# FPGA.net
KiCad netlist of a schematic drawn in Altium Designer
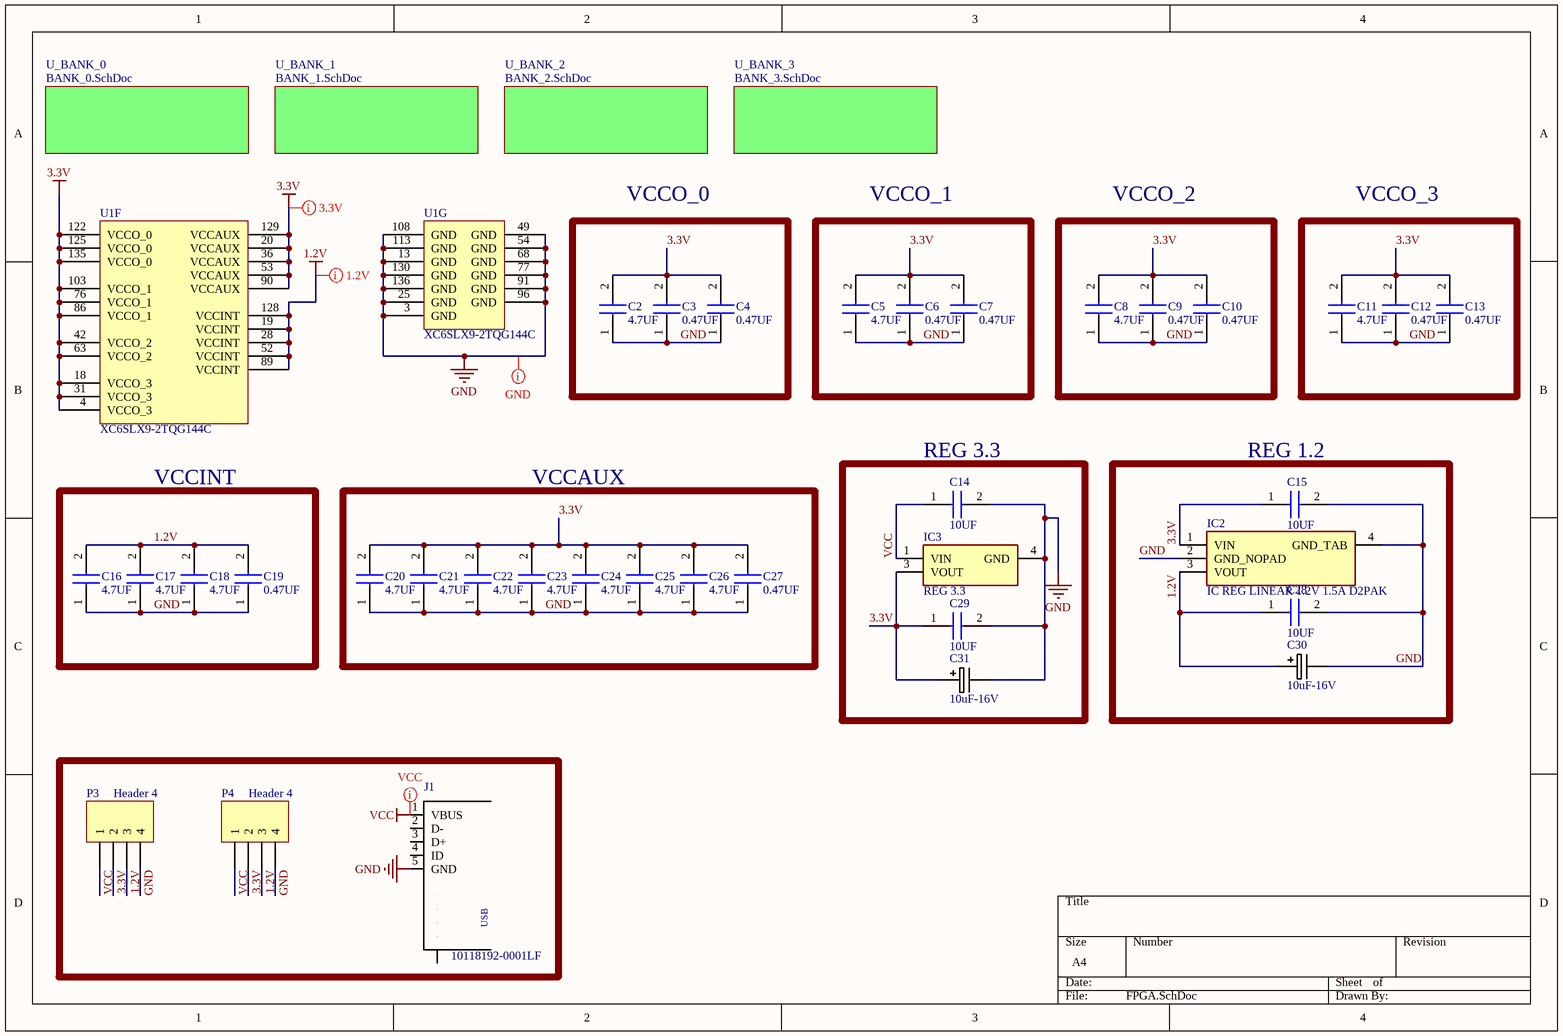
[diagram p0: FPGA.SchDoc]

(export (version "E")
  (design (tool "Eeschema 10.0.6"))
  (components
    (comp (ref "C2")
      (value "4.7UF")
      (footprint "PcbLib1:CAPC2012X135N")
      (description "Capacitor")
      (fields
        (field (name "MANUFACTURER_PART_NUMBER") "885012107013")
        (field (name "MOUSER PART NUMBER") "710-885012107013")
      )
      (libsource (lib "Schlib1_FPGA") (part "CAP CER 4.7UF 16V X5R 0805"))
    )
    (comp (ref "C3")
      (value "0.47UF")
      (footprint "PcbLib1:CAPC2012X135N")
      (description "Capacitor")
      (fields
        (field (name "MANUFACTURER_PART_NUMBER") "885012207049")
        (field (name "MOUSER PART NUMBER") "710-885012207049")
      )
      (libsource (lib "Schlib1_FPGA") (part "CAP CER 0.47UF 16V X7R 0805"))
    )
    (comp (ref "C4")
      (value "0.47UF")
      (footprint "PcbLib1:CAPC2012X135N")
      (description "Capacitor")
      (fields
        (field (name "MANUFACTURER_PART_NUMBER") "885012207049")
        (field (name "MOUSER PART NUMBER") "710-885012207049")
      )
      (libsource (lib "Schlib1_FPGA") (part "CAP CER 0.47UF 16V X7R 0805"))
    )
    (comp (ref "C5")
      (value "4.7UF")
      (footprint "PcbLib1:CAPC2012X135N")
      (description "Capacitor")
      (fields
        (field (name "MANUFACTURER_PART_NUMBER") "885012107013")
        (field (name "MOUSER PART NUMBER") "710-885012107013")
      )
      (libsource (lib "Schlib1_FPGA") (part "CAP CER 4.7UF 16V X5R 0805"))
    )
    (comp (ref "C6")
      (value "0.47UF")
      (footprint "PcbLib1:CAPC2012X135N")
      (description "Capacitor")
      (fields
        (field (name "MANUFACTURER_PART_NUMBER") "885012207049")
        (field (name "MOUSER PART NUMBER") "710-885012207049")
      )
      (libsource (lib "Schlib1_FPGA") (part "CAP CER 0.47UF 16V X7R 0805"))
    )
    (comp (ref "C7")
      (value "0.47UF")
      (footprint "PcbLib1:CAPC2012X135N")
      (description "Capacitor")
      (fields
        (field (name "MANUFACTURER_PART_NUMBER") "885012207049")
        (field (name "MOUSER PART NUMBER") "710-885012207049")
      )
      (libsource (lib "Schlib1_FPGA") (part "CAP CER 0.47UF 16V X7R 0805"))
    )
    (comp (ref "C8")
      (value "4.7UF")
      (footprint "PcbLib1:CAPC2012X135N")
      (description "Capacitor")
      (fields
        (field (name "MANUFACTURER_PART_NUMBER") "885012107013")
        (field (name "MOUSER PART NUMBER") "710-885012107013")
      )
      (libsource (lib "Schlib1_FPGA") (part "CAP CER 4.7UF 16V X5R 0805"))
    )
    (comp (ref "C9")
      (value "0.47UF")
      (footprint "PcbLib1:CAPC2012X135N")
      (description "Capacitor")
      (fields
        (field (name "MANUFACTURER_PART_NUMBER") "885012207049")
        (field (name "MOUSER PART NUMBER") "710-885012207049")
      )
      (libsource (lib "Schlib1_FPGA") (part "CAP CER 0.47UF 16V X7R 0805"))
    )
    (comp (ref "C10")
      (value "0.47UF")
      (footprint "PcbLib1:CAPC2012X135N")
      (description "Capacitor")
      (fields
        (field (name "MANUFACTURER_PART_NUMBER") "885012207049")
        (field (name "MOUSER PART NUMBER") "710-885012207049")
      )
      (libsource (lib "Schlib1_FPGA") (part "CAP CER 0.47UF 16V X7R 0805"))
    )
    (comp (ref "C11")
      (value "4.7UF")
      (footprint "PcbLib1:CAPC2012X135N")
      (description "Capacitor")
      (fields
        (field (name "MANUFACTURER_PART_NUMBER") "885012107013")
        (field (name "MOUSER PART NUMBER") "710-885012107013")
      )
      (libsource (lib "Schlib1_FPGA") (part "CAP CER 4.7UF 16V X5R 0805"))
    )
    (comp (ref "C12")
      (value "0.47UF")
      (footprint "PcbLib1:CAPC2012X135N")
      (description "Capacitor")
      (fields
        (field (name "MANUFACTURER_PART_NUMBER") "885012207049")
        (field (name "MOUSER PART NUMBER") "710-885012207049")
      )
      (libsource (lib "Schlib1_FPGA") (part "CAP CER 0.47UF 16V X7R 0805"))
    )
    (comp (ref "C13")
      (value "0.47UF")
      (footprint "PcbLib1:CAPC2012X135N")
      (description "Capacitor")
      (fields
        (field (name "MANUFACTURER_PART_NUMBER") "885012207049")
        (field (name "MOUSER PART NUMBER") "710-885012207049")
      )
      (libsource (lib "Schlib1_FPGA") (part "CAP CER 0.47UF 16V X7R 0805"))
    )
    (comp (ref "C14")
      (value "10UF")
      (footprint "PcbLib1:CAPC2012X135N")
      (description "Capacitor")
      (fields
        (field (name "MANUFACTURER_PART_NUMBER") "885012107013")
        (field (name "MOUSER PART NUMBER") "710-885012107013")
      )
      (libsource (lib "Schlib1_FPGA") (part "CAP CER 10UF 16V X5R 0805"))
    )
    (comp (ref "C15")
      (value "10UF")
      (footprint "PcbLib1:CAPC2012X135N")
      (description "Capacitor")
      (fields
        (field (name "MANUFACTURER_PART_NUMBER") "885012107013")
        (field (name "MOUSER PART NUMBER") "710-885012107013")
      )
      (libsource (lib "Schlib1_FPGA") (part "CAP CER 10UF 16V X5R 0805"))
    )
    (comp (ref "C16")
      (value "4.7UF")
      (footprint "PcbLib1:CAPC2012X135N")
      (description "Capacitor")
      (fields
        (field (name "MANUFACTURER_PART_NUMBER") "885012107013")
        (field (name "MOUSER PART NUMBER") "710-885012107013")
      )
      (libsource (lib "Schlib1_FPGA") (part "CAP CER 4.7UF 16V X5R 0805"))
    )
    (comp (ref "C17")
      (value "4.7UF")
      (footprint "PcbLib1:CAPC2012X135N")
      (description "Capacitor")
      (fields
        (field (name "MANUFACTURER_PART_NUMBER") "885012107013")
        (field (name "MOUSER PART NUMBER") "710-885012107013")
      )
      (libsource (lib "Schlib1_FPGA") (part "CAP CER 4.7UF 16V X5R 0805"))
    )
    (comp (ref "C18")
      (value "4.7UF")
      (footprint "CAPC2012X135N")
      (description "Capacitor")
      (fields
        (field (name "MANUFACTURER_PART_NUMBER") "885012107013")
        (field (name "MOUSER PART NUMBER") "710-885012107013")
      )
      (libsource (lib "Schlib1_FPGA") (part "CAP CER 4.7UF 16V X5R 0805"))
    )
    (comp (ref "C19")
      (value "0.47UF")
      (footprint "PcbLib1:CAPC2012X135N")
      (description "Capacitor")
      (fields
        (field (name "MANUFACTURER_PART_NUMBER") "885012207049")
        (field (name "MOUSER PART NUMBER") "710-885012207049")
      )
      (libsource (lib "Schlib1_FPGA") (part "CAP CER 0.47UF 16V X7R 0805"))
    )
    (comp (ref "C20")
      (value "4.7UF")
      (footprint "PcbLib1:CAPC2012X135N")
      (description "Capacitor")
      (fields
        (field (name "MANUFACTURER_PART_NUMBER") "885012107013")
        (field (name "MOUSER PART NUMBER") "710-885012107013")
      )
      (libsource (lib "Schlib1_FPGA") (part "CAP CER 4.7UF 16V X5R 0805"))
    )
    (comp (ref "C21")
      (value "4.7UF")
      (footprint "PcbLib1:CAPC2012X135N")
      (description "Capacitor")
      (fields
        (field (name "MANUFACTURER_PART_NUMBER") "885012107013")
        (field (name "MOUSER PART NUMBER") "710-885012107013")
      )
      (libsource (lib "Schlib1_FPGA") (part "CAP CER 4.7UF 16V X5R 0805"))
    )
    (comp (ref "C22")
      (value "4.7UF")
      (footprint "PcbLib1:CAPC2012X135N")
      (description "Capacitor")
      (fields
        (field (name "MANUFACTURER_PART_NUMBER") "885012107013")
        (field (name "MOUSER PART NUMBER") "710-885012107013")
      )
      (libsource (lib "Schlib1_FPGA") (part "CAP CER 4.7UF 16V X5R 0805"))
    )
    (comp (ref "C23")
      (value "4.7UF")
      (footprint "PcbLib1:CAPC2012X135N")
      (description "Capacitor")
      (fields
        (field (name "MANUFACTURER_PART_NUMBER") "885012107013")
        (field (name "MOUSER PART NUMBER") "710-885012107013")
      )
      (libsource (lib "Schlib1_FPGA") (part "CAP CER 4.7UF 16V X5R 0805"))
    )
    (comp (ref "C24")
      (value "4.7UF")
      (footprint "PcbLib1:CAPC2012X135N")
      (description "Capacitor")
      (fields
        (field (name "MANUFACTURER_PART_NUMBER") "885012107013")
        (field (name "MOUSER PART NUMBER") "710-885012107013")
      )
      (libsource (lib "Schlib1_FPGA") (part "CAP CER 4.7UF 16V X5R 0805"))
    )
    (comp (ref "C25")
      (value "4.7UF")
      (footprint "PcbLib1:CAPC2012X135N")
      (description "Capacitor")
      (fields
        (field (name "MANUFACTURER_PART_NUMBER") "885012107013")
        (field (name "MOUSER PART NUMBER") "710-885012107013")
      )
      (libsource (lib "Schlib1_FPGA") (part "CAP CER 4.7UF 16V X5R 0805"))
    )
    (comp (ref "C26")
      (value "4.7UF")
      (footprint "PcbLib1:CAPC2012X135N")
      (description "Capacitor")
      (fields
        (field (name "MANUFACTURER_PART_NUMBER") "885012107013")
        (field (name "MOUSER PART NUMBER") "710-885012107013")
      )
      (libsource (lib "Schlib1_FPGA") (part "CAP CER 4.7UF 16V X5R 0805"))
    )
    (comp (ref "C27")
      (value "0.47UF")
      (footprint "PcbLib1:CAPC2012X135N")
      (description "Capacitor")
      (fields
        (field (name "MANUFACTURER_PART_NUMBER") "885012207049")
        (field (name "MOUSER PART NUMBER") "710-885012207049")
      )
      (libsource (lib "Schlib1_FPGA") (part "CAP CER 0.47UF 16V X7R 0805"))
    )
    (comp (ref "C28")
      (value "10UF")
      (footprint "PcbLib1:CAPC2012X135N")
      (description "Capacitor")
      (fields
        (field (name "MANUFACTURER_PART_NUMBER") "885012107013")
        (field (name "MOUSER PART NUMBER") "710-885012107013")
      )
      (libsource (lib "Schlib1_FPGA") (part "CAP CER 10UF 16V X5R 0805"))
    )
    (comp (ref "C29")
      (value "10UF")
      (footprint "PcbLib1:CAPC2012X135N")
      (description "Capacitor")
      (fields
        (field (name "MANUFACTURER_PART_NUMBER") "885012107013")
        (field (name "MOUSER PART NUMBER") "710-885012107013")
      )
      (libsource (lib "Schlib1_FPGA") (part "CAP CER 10UF 16V X5R 0805"))
    )
    (comp (ref "C30")
      (value "10uF-16V")
      (footprint "PANACAP-b")
      (description "GENERIC CAPACITOR POLARISED")
      (libsource (lib "vh_altium_library") (part "PANACAP-10UF-16V-FK"))
    )
    (comp (ref "C31")
      (value "10uF-16V")
      (footprint "PANACAP-b")
      (description "GENERIC CAPACITOR POLARISED")
      (libsource (lib "vh_altium_library") (part "PANACAP-10UF-16V-FK"))
    )
    (comp (ref "IC2")
      (value "IC REG LINEAR 1.2V 1.5A D2PAK")
      (footprint "PcbLib1:TO254P1420X457-4N")
      (description "Integrated Circuit")
      (fields
        (field (name "MANUFACTURER_PART_NUMBER") "NCP565D2T12G")
        (field (name "MOUSER PART NUMBER") "863-NCP565D2T12G")
      )
      (libsource (lib "Schlib1_FPGA") (part "IC REG LINEAR 1.2V 1.5A D2PAK"))
    )
    (comp (ref "IC3")
      (value "REG 3.3")
      (footprint "PcbLib1:NCV8674DS50R4G")
      (description "Integrated Circuit")
      (fields
        (field (name "MANUFACTURER_PART_NUMBER") "NCP565D2T33R4G")
        (field (name "MOUSER PART NUMBER") "863-NCP565D2T33R4G")
      )
      (libsource (lib "Schlib1_FPGA") (part "IC REG LINEAR 3.3V 1.5A D2PAK"))
    )
    (comp (ref "J1")
      (value "10118192-0001LF")
      (footprint "10118192-0001LF_10118192-0001LF(Primary)")
      (description "Conn Micro USB Type B RCP 5 POS 0.65mm Solder RA SMD 5 Terminal 1 Port T/R")
      (fields (field (name "MF") "Amphenol"))
      (libsource (lib "USB Micro Port") (part "10118192-0001LF"))
    )
    (comp (ref "P3")
      (value "Header 4")
      (footprint "HDR1X4")
      (description "Header, 4-Pin")
      (fields (field (name "PUBLISHER") "Altium Limited"))
      (libsource (lib "Miscellaneous Connectors") (part "Header 4"))
    )
    (comp (ref "P4")
      (value "Header 4")
      (footprint "HDR1X4")
      (description "Header, 4-Pin")
      (fields (field (name "PUBLISHER") "Altium Limited"))
      (libsource (lib "Miscellaneous Connectors") (part "Header 4"))
    )
    (comp (ref "U1")
      (value "XC6SLX9-2TQG144C")
      (footprint "TQG144_N")
      (libsource (lib "Xilinx Spartan-6") (part "XC6SLX9-2TQG144C"))
    )
  )
  (nets
    (net (code "1") (name "1.2V") (class "Default")
      (node (ref "C16") (pin "2") (pinfunction "2_2") (pintype "passive"))
      (node (ref "C17") (pin "2") (pinfunction "2_2") (pintype "passive"))
      (node (ref "C18") (pin "2") (pinfunction "2_2") (pintype "passive"))
      (node (ref "C19") (pin "2") (pinfunction "2_2") (pintype "passive"))
      (node (ref "C28") (pin "1") (pinfunction "1_1") (pintype "passive"))
      (node (ref "C30") (pin "+") (pinfunction "+_+") (pintype "passive"))
      (node (ref "IC2") (pin "3") (pinfunction "VOUT_3") (pintype "power_in"))
      (node (ref "P3") (pin "3") (pinfunction "3_3") (pintype "passive"))
      (node (ref "P4") (pin "3") (pinfunction "3_3") (pintype "passive"))
      (node (ref "U1") (pin "128") (pinfunction "VCCINT_128") (pintype "power_in"))
      (node (ref "U1") (pin "19") (pinfunction "VCCINT_19") (pintype "power_in"))
      (node (ref "U1") (pin "28") (pinfunction "VCCINT_28") (pintype "power_in"))
      (node (ref "U1") (pin "52") (pinfunction "VCCINT_52") (pintype "power_in"))
      (node (ref "U1") (pin "89") (pinfunction "VCCINT_89") (pintype "power_in"))
    )
    (net (code "2") (name "3.3V") (class "Default")
      (node (ref "C10") (pin "2") (pinfunction "2_2") (pintype "passive"))
      (node (ref "C11") (pin "2") (pinfunction "2_2") (pintype "passive"))
      (node (ref "C12") (pin "2") (pinfunction "2_2") (pintype "passive"))
      (node (ref "C13") (pin "2") (pinfunction "2_2") (pintype "passive"))
      (node (ref "C15") (pin "1") (pinfunction "1_1") (pintype "passive"))
      (node (ref "C2") (pin "2") (pinfunction "2_2") (pintype "passive"))
      (node (ref "C20") (pin "2") (pinfunction "2_2") (pintype "passive"))
      (node (ref "C21") (pin "2") (pinfunction "2_2") (pintype "passive"))
      (node (ref "C22") (pin "2") (pinfunction "2_2") (pintype "passive"))
      (node (ref "C23") (pin "2") (pinfunction "2_2") (pintype "passive"))
      (node (ref "C24") (pin "2") (pinfunction "2_2") (pintype "passive"))
      (node (ref "C25") (pin "2") (pinfunction "2_2") (pintype "passive"))
      (node (ref "C26") (pin "2") (pinfunction "2_2") (pintype "passive"))
      (node (ref "C27") (pin "2") (pinfunction "2_2") (pintype "passive"))
      (node (ref "C29") (pin "1") (pinfunction "1_1") (pintype "passive"))
      (node (ref "C3") (pin "2") (pinfunction "2_2") (pintype "passive"))
      (node (ref "C31") (pin "+") (pinfunction "+_+") (pintype "passive"))
      (node (ref "C4") (pin "2") (pinfunction "2_2") (pintype "passive"))
      (node (ref "C5") (pin "2") (pinfunction "2_2") (pintype "passive"))
      (node (ref "C6") (pin "2") (pinfunction "2_2") (pintype "passive"))
      (node (ref "C7") (pin "2") (pinfunction "2_2") (pintype "passive"))
      (node (ref "C8") (pin "2") (pinfunction "2_2") (pintype "passive"))
      (node (ref "C9") (pin "2") (pinfunction "2_2") (pintype "passive"))
      (node (ref "IC2") (pin "1") (pinfunction "VIN_1") (pintype "power_in"))
      (node (ref "IC3") (pin "3") (pinfunction "VOUT_3") (pintype "power_in"))
      (node (ref "P3") (pin "2") (pinfunction "2_2") (pintype "passive"))
      (node (ref "P4") (pin "2") (pinfunction "2_2") (pintype "passive"))
      (node (ref "U1") (pin "103") (pinfunction "VCCO_1_103") (pintype "power_in"))
      (node (ref "U1") (pin "122") (pinfunction "VCCO_0_122") (pintype "power_in"))
      (node (ref "U1") (pin "125") (pinfunction "VCCO_0_125") (pintype "power_in"))
      (node (ref "U1") (pin "129") (pinfunction "VCCAUX_129") (pintype "power_in"))
      (node (ref "U1") (pin "135") (pinfunction "VCCO_0_135") (pintype "power_in"))
      (node (ref "U1") (pin "18") (pinfunction "VCCO_3_18") (pintype "power_in"))
      (node (ref "U1") (pin "20") (pinfunction "VCCAUX_20") (pintype "power_in"))
      (node (ref "U1") (pin "31") (pinfunction "VCCO_3_31") (pintype "power_in"))
      (node (ref "U1") (pin "36") (pinfunction "VCCAUX_36") (pintype "power_in"))
      (node (ref "U1") (pin "4") (pinfunction "VCCO_3_4") (pintype "power_in"))
      (node (ref "U1") (pin "42") (pinfunction "VCCO_2_42") (pintype "power_in"))
      (node (ref "U1") (pin "53") (pinfunction "VCCAUX_53") (pintype "power_in"))
      (node (ref "U1") (pin "63") (pinfunction "VCCO_2_63") (pintype "power_in"))
      (node (ref "U1") (pin "76") (pinfunction "VCCO_1_76") (pintype "power_in"))
      (node (ref "U1") (pin "86") (pinfunction "VCCO_1_86") (pintype "power_in"))
      (node (ref "U1") (pin "90") (pinfunction "VCCAUX_90") (pintype "power_in"))
    )
    (net (code "3") (name "GND") (class "Default")
      (node (ref "C10") (pin "1") (pinfunction "1_1") (pintype "passive"))
      (node (ref "C11") (pin "1") (pinfunction "1_1") (pintype "passive"))
      (node (ref "C12") (pin "1") (pinfunction "1_1") (pintype "passive"))
      (node (ref "C13") (pin "1") (pinfunction "1_1") (pintype "passive"))
      (node (ref "C14") (pin "2") (pinfunction "2_2") (pintype "passive"))
      (node (ref "C15") (pin "2") (pinfunction "2_2") (pintype "passive"))
      (node (ref "C16") (pin "1") (pinfunction "1_1") (pintype "passive"))
      (node (ref "C17") (pin "1") (pinfunction "1_1") (pintype "passive"))
      (node (ref "C18") (pin "1") (pinfunction "1_1") (pintype "passive"))
      (node (ref "C19") (pin "1") (pinfunction "1_1") (pintype "passive"))
      (node (ref "C2") (pin "1") (pinfunction "1_1") (pintype "passive"))
      (node (ref "C20") (pin "1") (pinfunction "1_1") (pintype "passive"))
      (node (ref "C21") (pin "1") (pinfunction "1_1") (pintype "passive"))
      (node (ref "C22") (pin "1") (pinfunction "1_1") (pintype "passive"))
      (node (ref "C23") (pin "1") (pinfunction "1_1") (pintype "passive"))
      (node (ref "C24") (pin "1") (pinfunction "1_1") (pintype "passive"))
      (node (ref "C25") (pin "1") (pinfunction "1_1") (pintype "passive"))
      (node (ref "C26") (pin "1") (pinfunction "1_1") (pintype "passive"))
      (node (ref "C27") (pin "1") (pinfunction "1_1") (pintype "passive"))
      (node (ref "C28") (pin "2") (pinfunction "2_2") (pintype "passive"))
      (node (ref "C29") (pin "2") (pinfunction "2_2") (pintype "passive"))
      (node (ref "C3") (pin "1") (pinfunction "1_1") (pintype "passive"))
      (node (ref "C30") (pin "-") (pinfunction "-_-") (pintype "passive"))
      (node (ref "C31") (pin "-") (pinfunction "-_-") (pintype "passive"))
      (node (ref "C4") (pin "1") (pinfunction "1_1") (pintype "passive"))
      (node (ref "C5") (pin "1") (pinfunction "1_1") (pintype "passive"))
      (node (ref "C6") (pin "1") (pinfunction "1_1") (pintype "passive"))
      (node (ref "C7") (pin "1") (pinfunction "1_1") (pintype "passive"))
      (node (ref "C8") (pin "1") (pinfunction "1_1") (pintype "passive"))
      (node (ref "C9") (pin "1") (pinfunction "1_1") (pintype "passive"))
      (node (ref "IC2") (pin "2") (pinfunction "GND_NOPAD_2") (pintype "power_in"))
      (node (ref "IC2") (pin "4") (pinfunction "GND_TAB_4") (pintype "power_in"))
      (node (ref "IC3") (pin "4") (pinfunction "GND_4") (pintype "power_in"))
      (node (ref "J1") (pin "5") (pinfunction "GND_5") (pintype "passive"))
      (node (ref "P3") (pin "4") (pinfunction "4_4") (pintype "passive"))
      (node (ref "P4") (pin "4") (pinfunction "4_4") (pintype "passive"))
      (node (ref "U1") (pin "108") (pinfunction "GND_108") (pintype "power_in"))
      (node (ref "U1") (pin "113") (pinfunction "GND_113") (pintype "power_in"))
      (node (ref "U1") (pin "13") (pinfunction "GND_13") (pintype "power_in"))
      (node (ref "U1") (pin "130") (pinfunction "GND_130") (pintype "power_in"))
      (node (ref "U1") (pin "136") (pinfunction "GND_136") (pintype "power_in"))
      (node (ref "U1") (pin "25") (pinfunction "GND_25") (pintype "power_in"))
      (node (ref "U1") (pin "3") (pinfunction "GND_3") (pintype "power_in"))
      (node (ref "U1") (pin "49") (pinfunction "GND_49") (pintype "power_in"))
      (node (ref "U1") (pin "54") (pinfunction "GND_54") (pintype "power_in"))
      (node (ref "U1") (pin "68") (pinfunction "GND_68") (pintype "power_in"))
      (node (ref "U1") (pin "77") (pinfunction "GND_77") (pintype "power_in"))
      (node (ref "U1") (pin "91") (pinfunction "GND_91") (pintype "power_in"))
      (node (ref "U1") (pin "96") (pinfunction "GND_96") (pintype "power_in"))
    )
    (net (code "4") (name "VCC") (class "Default")
      (node (ref "C14") (pin "1") (pinfunction "1_1") (pintype "passive"))
      (node (ref "IC3") (pin "1") (pinfunction "VIN_1") (pintype "power_in"))
      (node (ref "J1") (pin "1") (pinfunction "VBUS_1") (pintype "passive"))
      (node (ref "P3") (pin "1") (pinfunction "1_1") (pintype "passive"))
      (node (ref "P4") (pin "1") (pinfunction "1_1") (pintype "passive"))
    )
    (net (code "5") (name "unconnected-(J1-D+-Pad3)") (class "Default")
      (node (ref "J1") (pin "3") (pinfunction "D+_3") (pintype "passive"))
    )
    (net (code "6") (name "unconnected-(J1-D--Pad2)") (class "Default")
      (node (ref "J1") (pin "2") (pinfunction "D-_2") (pintype "passive"))
    )
    (net (code "7") (name "unconnected-(J1-ID-Pad4)") (class "Default")
      (node (ref "J1") (pin "4") (pinfunction "ID_4") (pintype "passive"))
    )
    (net (code "8") (name "unconnected-(J1-S-PadM1)") (class "Default")
      (node (ref "J1") (pin "M1") (pinfunction "S_M1") (pintype "passive"))
    )
    (net (code "9") (name "unconnected-(J1-S-PadM2)") (class "Default")
      (node (ref "J1") (pin "M2") (pinfunction "S_M2") (pintype "passive"))
    )
    (net (code "10") (name "unconnected-(J1-S-PadS1)") (class "Default")
      (node (ref "J1") (pin "S1") (pinfunction "S_S1") (pintype "passive"))
    )
    (net (code "11") (name "unconnected-(J1-S-PadS2)") (class "Default")
      (node (ref "J1") (pin "S2") (pinfunction "S_S2") (pintype "passive"))
    )
    (net (code "12") (name "unconnected-(J1-S-PadS3)") (class "Default")
      (node (ref "J1") (pin "S3") (pinfunction "S_S3") (pintype "passive"))
    )
    (net (code "13") (name "unconnected-(J1-S-PadS4)") (class "Default")
      (node (ref "J1") (pin "S4") (pinfunction "S_S4") (pintype "passive"))
    )
  )
)
